# serial_port.net
KiCad netlist of a schematic drawn in Altium Designer
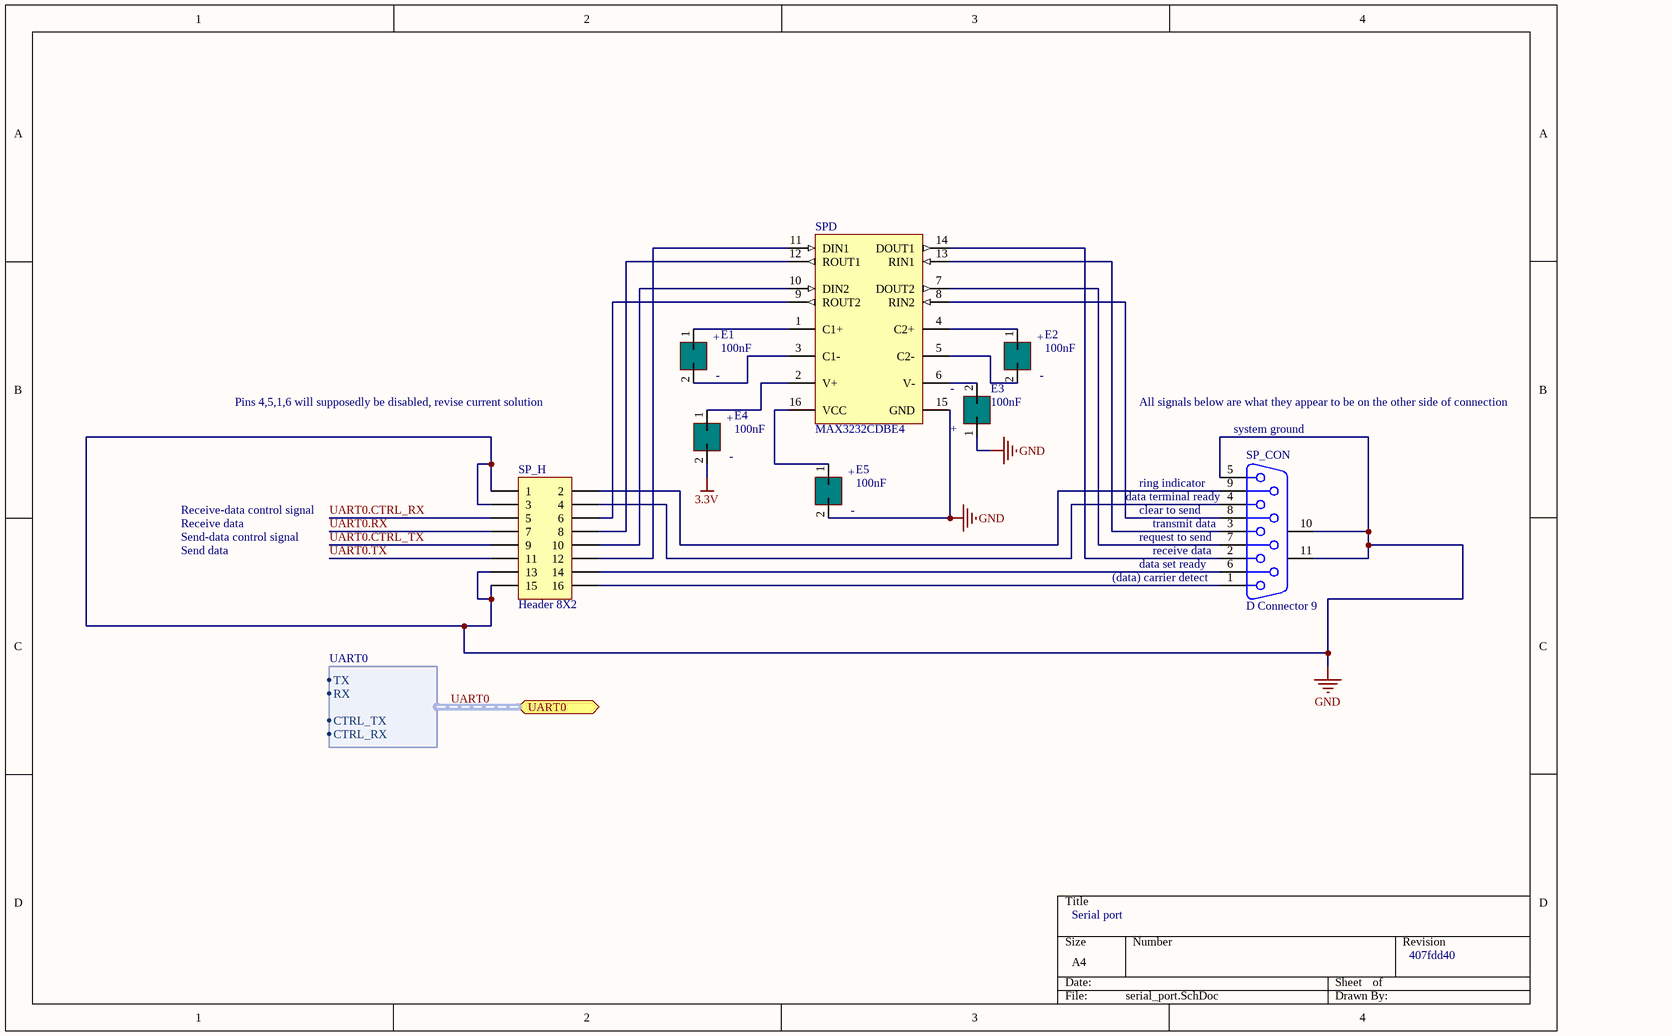
[diagram p0: serial_port.SchDoc]

(export (version "E")
  (design (tool "Eeschema 10.0.6"))
  (components
    (comp (ref "E1")
      (value "100nF")
      (footprint "cap_pol_size_B")
      (description "size B series S type V capacitor, panasonic elec")
      (libsource (lib "cap-pol-size-B") (part "CAP_POL_SIZE_B"))
    )
    (comp (ref "E2")
      (value "100nF")
      (footprint "cap_pol_size_B")
      (description "size B series S type V capacitor, panasonic elec")
      (libsource (lib "cap-pol-size-B") (part "CAP_POL_SIZE_B"))
    )
    (comp (ref "E3")
      (value "100nF")
      (footprint "cap_pol_size_B")
      (description "size B series S type V capacitor, panasonic elec")
      (libsource (lib "") (part "CAP_POL_SIZE_B_1"))
    )
    (comp (ref "E4")
      (value "100nF")
      (footprint "cap_pol_size_B")
      (description "size B series S type V capacitor, panasonic elec")
      (libsource (lib "cap-pol-size-B") (part "CAP_POL_SIZE_B"))
    )
    (comp (ref "E5")
      (value "100nF")
      (footprint "cap_pol_size_B")
      (description "size B series S type V capacitor, panasonic elec")
      (libsource (lib "cap-pol-size-B") (part "CAP_POL_SIZE_B"))
    )
    (comp (ref "SPD")
      (value "MAX3232CDBE4")
      (footprint "TI-DB16_L")
      (libsource (lib "Altium Content Vault") (part "TI-MAX3232-SSOP_DB-16"))
    )
    (comp (ref "SP_CON")
      (value "D Connector 9")
      (footprint "DSUB1.385-2H9")
      (description "Receptacle Assembly, 9 Position, Right Angle")
      (fields (field (name "PUBLISHER") "Altium Limited"))
      (libsource (lib "Miscellaneous Connectors") (part "D Connector 9"))
    )
    (comp (ref "SP_H")
      (value "Header 8X2")
      (footprint "HDR2X8")
      (description "Header, 8-Pin, Dual row")
      (fields (field (name "PUBLISHER") "Altium Limited"))
      (libsource (lib "Miscellaneous Connectors") (part "Header 8X2"))
    )
  )
  (nets
    (net (code "2") (name "/UART0.CTRL_RX") (class "Default")
      (node (ref "SP_H") (pin "5") (pinfunction "5_5") (pintype "passive"))
    )
    (net (code "3") (name "/UART0.CTRL_TX") (class "Default")
      (node (ref "SP_H") (pin "9") (pinfunction "9_9") (pintype "passive"))
    )
    (net (code "4") (name "/UART0.RX") (class "Default")
      (node (ref "SP_H") (pin "7") (pinfunction "7_7") (pintype "passive"))
    )
    (net (code "5") (name "/UART0.TX") (class "Default")
      (node (ref "SP_H") (pin "11") (pinfunction "11_11") (pintype "passive"))
    )
    (net (code "7") (name "3.3V") (class "Default")
      (node (ref "E4") (pin "2") (pinfunction "2_2") (pintype "passive"))
    )
    (net (code "8") (name "GND") (class "Default")
      (node (ref "E3") (pin "1") (pinfunction "1_1") (pintype "passive"))
      (node (ref "E5") (pin "2") (pinfunction "2_2") (pintype "passive"))
      (node (ref "SPD") (pin "15") (pinfunction "GND_15") (pintype "power_in"))
      (node (ref "SP_CON") (pin "10") (pinfunction "MH1_10") (pintype "passive"))
      (node (ref "SP_CON") (pin "11") (pinfunction "MH2_11") (pintype "passive"))
      (node (ref "SP_CON") (pin "5") (pinfunction "5_5") (pintype "passive"))
      (node (ref "SP_H") (pin "1") (pinfunction "1_1") (pintype "passive"))
      (node (ref "SP_H") (pin "13") (pinfunction "13_13") (pintype "passive"))
      (node (ref "SP_H") (pin "15") (pinfunction "15_15") (pintype "passive"))
      (node (ref "SP_H") (pin "3") (pinfunction "3_3") (pintype "passive"))
    )
    (net (code "9") (name "Net-(SPD-C1+)") (class "Default")
      (node (ref "E1") (pin "1") (pinfunction "1_1") (pintype "passive"))
      (node (ref "SPD") (pin "1") (pinfunction "C1+_1") (pintype "passive"))
    )
    (net (code "10") (name "Net-(SPD-C1-)") (class "Default")
      (node (ref "E1") (pin "2") (pinfunction "2_2") (pintype "passive"))
      (node (ref "SPD") (pin "3") (pinfunction "C1-_3") (pintype "passive"))
    )
    (net (code "11") (name "Net-(SPD-C2+)") (class "Default")
      (node (ref "E2") (pin "1") (pinfunction "1_1") (pintype "passive"))
      (node (ref "SPD") (pin "4") (pinfunction "C2+_4") (pintype "passive"))
    )
    (net (code "12") (name "Net-(SPD-C2-)") (class "Default")
      (node (ref "E2") (pin "2") (pinfunction "2_2") (pintype "passive"))
      (node (ref "SPD") (pin "5") (pinfunction "C2-_5") (pintype "passive"))
    )
    (net (code "13") (name "Net-(SPD-DIN1)") (class "Default")
      (node (ref "SPD") (pin "11") (pinfunction "DIN1_11") (pintype "input"))
      (node (ref "SP_H") (pin "12") (pinfunction "12_12") (pintype "passive"))
    )
    (net (code "14") (name "Net-(SPD-DIN2)") (class "Default")
      (node (ref "SPD") (pin "10") (pinfunction "DIN2_10") (pintype "input"))
      (node (ref "SP_H") (pin "10") (pinfunction "10_10") (pintype "passive"))
    )
    (net (code "15") (name "Net-(SPD-DOUT1)") (class "Default")
      (node (ref "SPD") (pin "14") (pinfunction "DOUT1_14") (pintype "output"))
      (node (ref "SP_CON") (pin "2") (pinfunction "2_2") (pintype "passive"))
    )
    (net (code "16") (name "Net-(SPD-DOUT2)") (class "Default")
      (node (ref "SPD") (pin "7") (pinfunction "DOUT2_7") (pintype "output"))
      (node (ref "SP_CON") (pin "7") (pinfunction "7_7") (pintype "passive"))
    )
    (net (code "17") (name "Net-(SPD-RIN1)") (class "Default")
      (node (ref "SPD") (pin "13") (pinfunction "RIN1_13") (pintype "input"))
      (node (ref "SP_CON") (pin "3") (pinfunction "3_3") (pintype "passive"))
    )
    (net (code "18") (name "Net-(SPD-RIN2)") (class "Default")
      (node (ref "SPD") (pin "8") (pinfunction "RIN2_8") (pintype "input"))
      (node (ref "SP_CON") (pin "8") (pinfunction "8_8") (pintype "passive"))
    )
    (net (code "19") (name "Net-(SPD-ROUT1)") (class "Default")
      (node (ref "SPD") (pin "12") (pinfunction "ROUT1_12") (pintype "output"))
      (node (ref "SP_H") (pin "8") (pinfunction "8_8") (pintype "passive"))
    )
    (net (code "20") (name "Net-(SPD-ROUT2)") (class "Default")
      (node (ref "SPD") (pin "9") (pinfunction "ROUT2_9") (pintype "output"))
      (node (ref "SP_H") (pin "6") (pinfunction "6_6") (pintype "passive"))
    )
    (net (code "21") (name "Net-(SPD-V+)") (class "Default")
      (node (ref "E4") (pin "1") (pinfunction "1_1") (pintype "passive"))
      (node (ref "SPD") (pin "2") (pinfunction "V+_2") (pintype "power_in"))
    )
    (net (code "22") (name "Net-(SPD-V-)") (class "Default")
      (node (ref "E3") (pin "2") (pinfunction "2_2") (pintype "passive"))
      (node (ref "SPD") (pin "6") (pinfunction "V-_6") (pintype "power_in"))
    )
    (net (code "23") (name "Net-(SPD-VCC)") (class "Default")
      (node (ref "E5") (pin "1") (pinfunction "1_1") (pintype "passive"))
      (node (ref "SPD") (pin "16") (pinfunction "VCC_16") (pintype "power_in"))
    )
    (net (code "24") (name "Net-(SP_CON-Pad1)") (class "Default")
      (node (ref "SP_CON") (pin "1") (pinfunction "1_1") (pintype "passive"))
      (node (ref "SP_H") (pin "16") (pinfunction "16_16") (pintype "passive"))
    )
    (net (code "25") (name "Net-(SP_CON-Pad4)") (class "Default")
      (node (ref "SP_CON") (pin "4") (pinfunction "4_4") (pintype "passive"))
      (node (ref "SP_H") (pin "4") (pinfunction "4_4") (pintype "passive"))
    )
    (net (code "26") (name "Net-(SP_CON-Pad6)") (class "Default")
      (node (ref "SP_CON") (pin "6") (pinfunction "6_6") (pintype "passive"))
      (node (ref "SP_H") (pin "14") (pinfunction "14_14") (pintype "passive"))
    )
    (net (code "27") (name "Net-(SP_CON-Pad9)") (class "Default")
      (node (ref "SP_CON") (pin "9") (pinfunction "9_9") (pintype "passive"))
      (node (ref "SP_H") (pin "2") (pinfunction "2_2") (pintype "passive"))
    )
  )
)
